# harp_load_cells_interface_v1_1.net
KiCad netlist of a schematic drawn in EAGLE
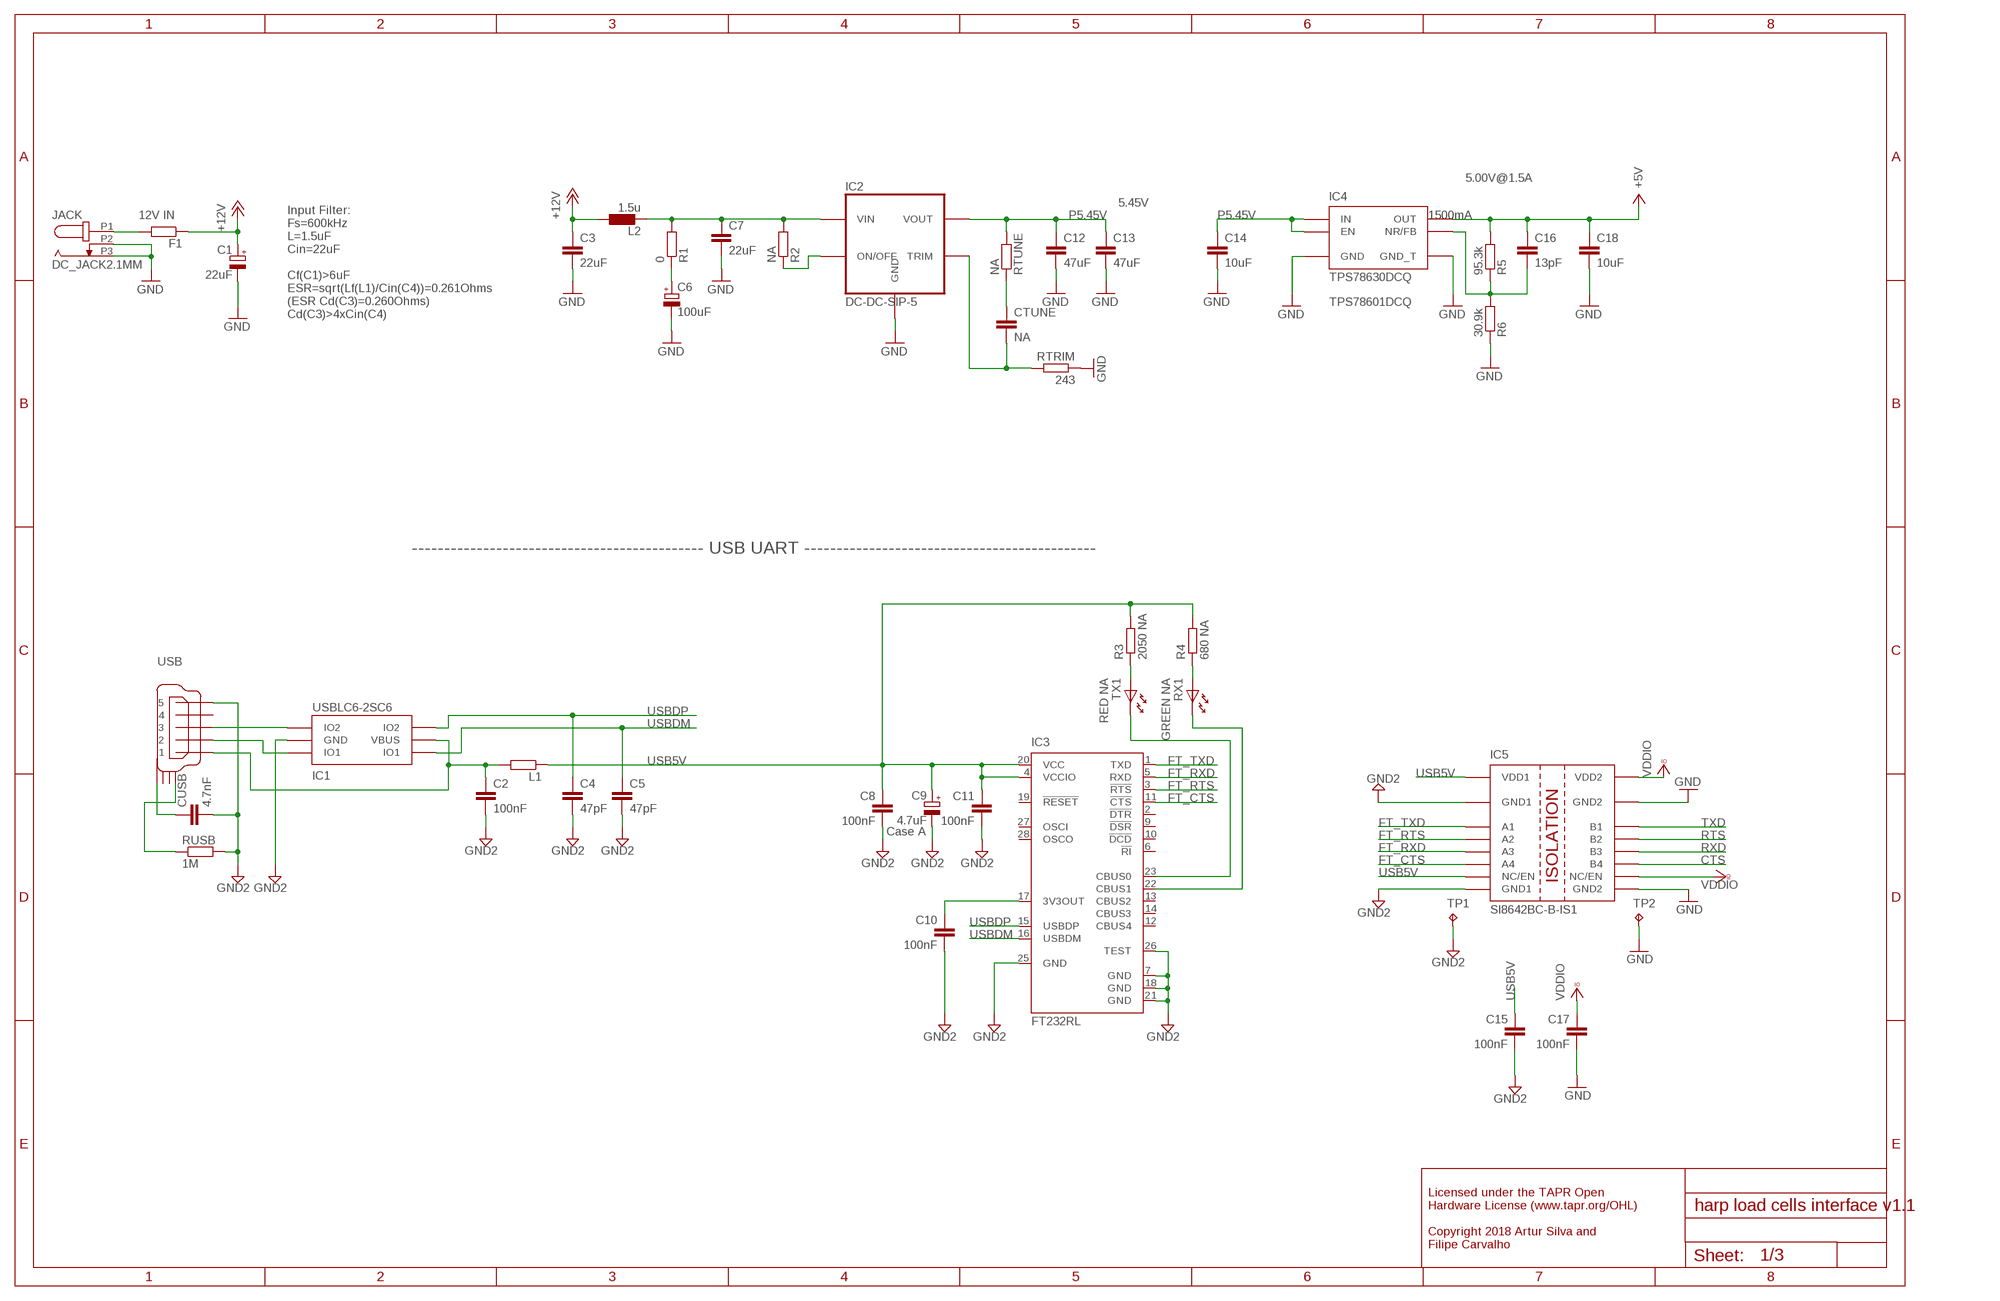
[diagram p0: schematic, sheet 1]
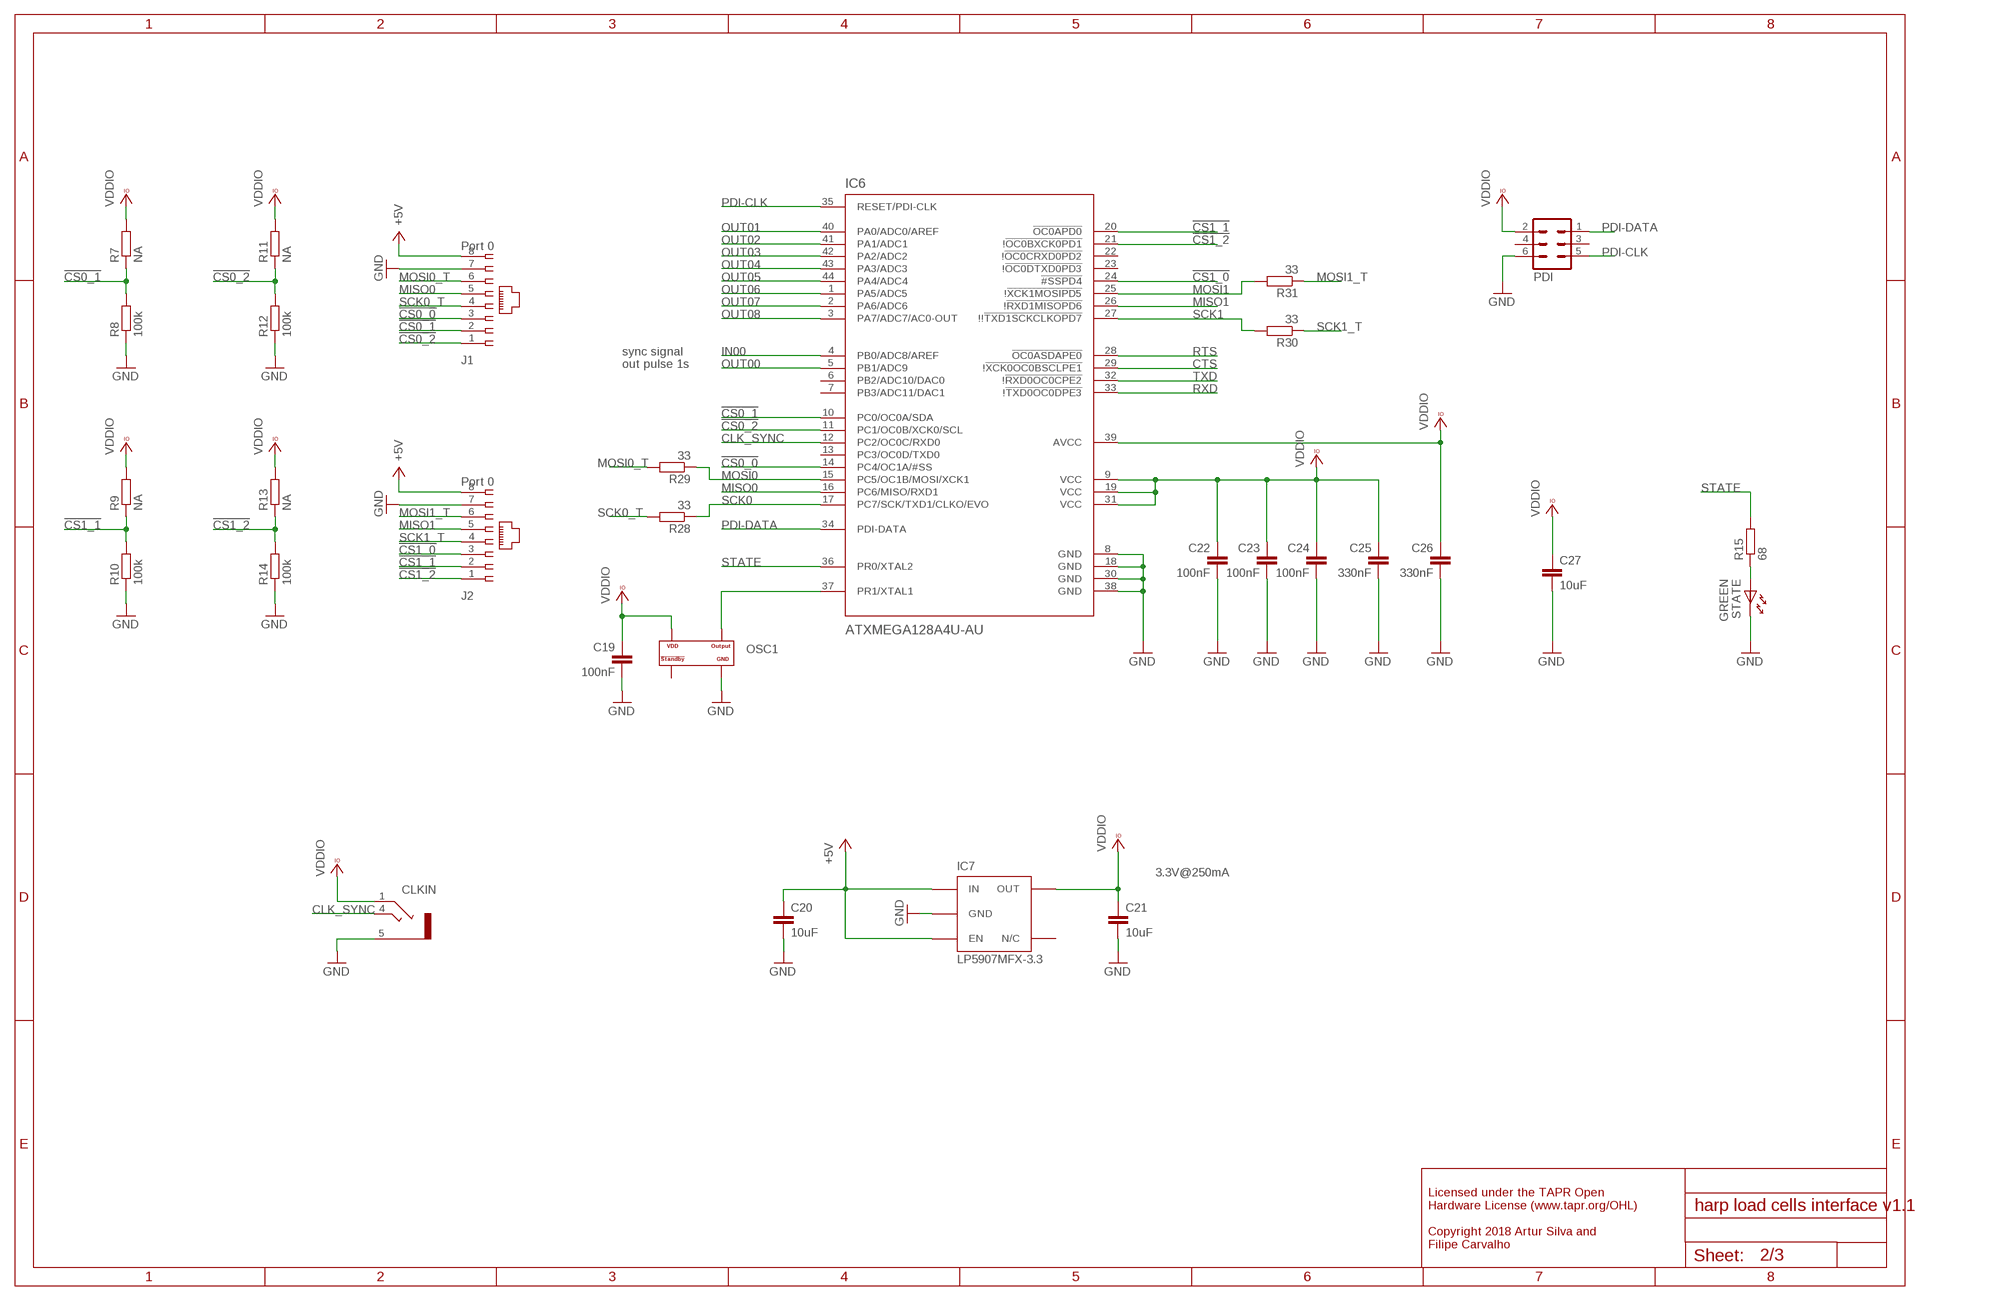
[diagram p1: schematic, sheet 2]
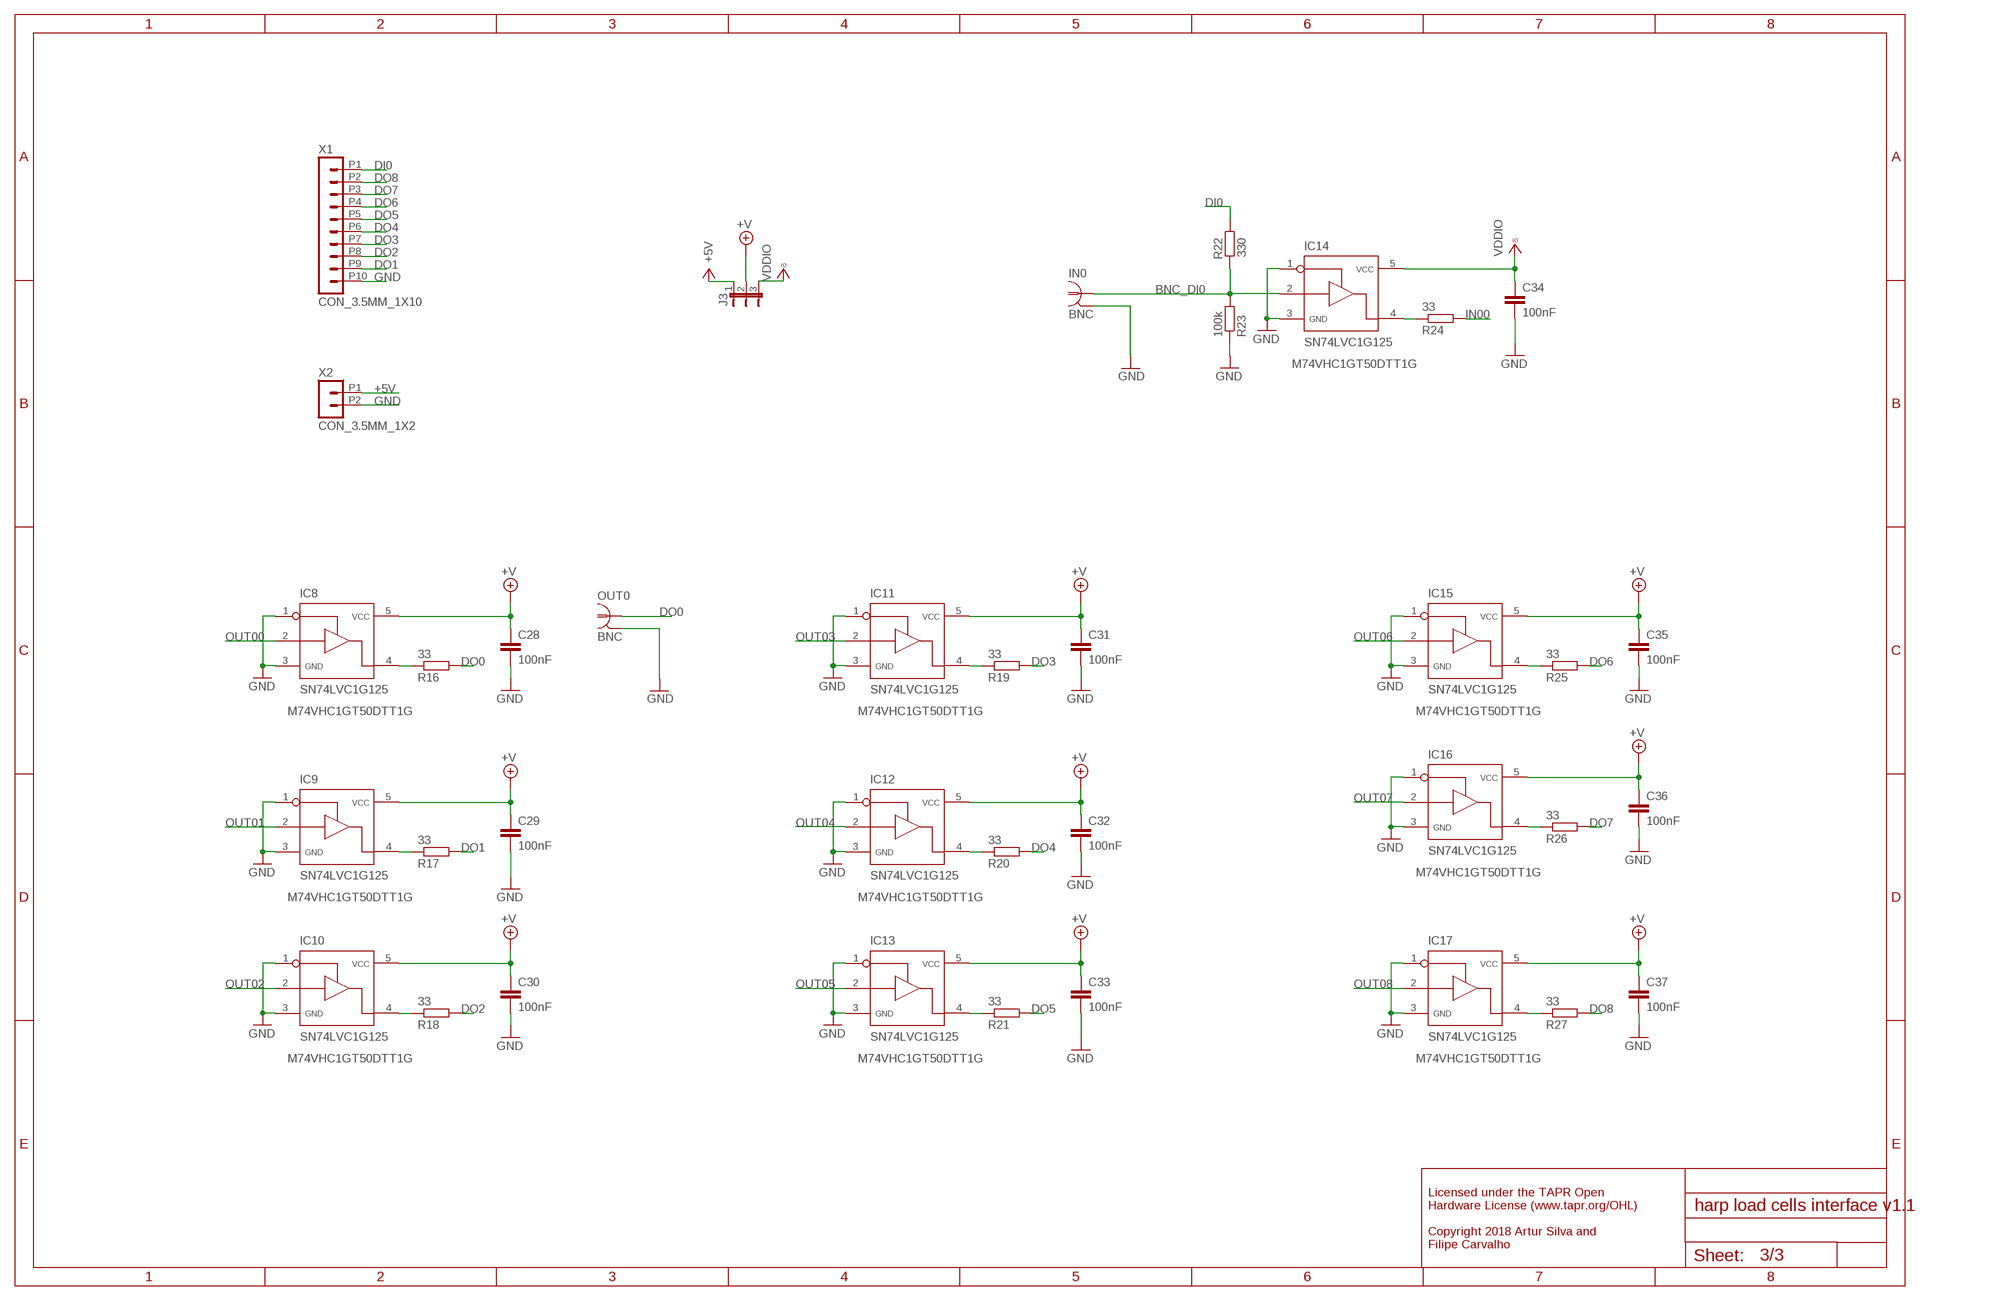
[diagram p2: schematic, sheet 3]

(export (version "E")
  (design (tool "Eeschema 10.0.6"))
  (components
    (comp (ref "C19")
      (value "100nF")
      (footprint "eagle-import:C0402")
      (libsource (lib "eagle-import") (part "C-EUC0402"))
    )
    (comp (ref "C20")
      (value "10uF")
      (footprint "eagle-import:C0603")
      (libsource (lib "eagle-import") (part "C-EUC0603"))
    )
    (comp (ref "C21")
      (value "10uF")
      (footprint "eagle-import:C0603")
      (libsource (lib "eagle-import") (part "C-EUC0603"))
    )
    (comp (ref "C22")
      (value "100nF")
      (footprint "eagle-import:C0402")
      (libsource (lib "eagle-import") (part "C-EUC0402"))
    )
    (comp (ref "C23")
      (value "100nF")
      (footprint "eagle-import:C0402")
      (libsource (lib "eagle-import") (part "C-EUC0402"))
    )
    (comp (ref "C24")
      (value "100nF")
      (footprint "eagle-import:C0402")
      (libsource (lib "eagle-import") (part "C-EUC0402"))
    )
    (comp (ref "C25")
      (value "330nF")
      (footprint "eagle-import:C0402")
      (libsource (lib "eagle-import") (part "C-EUC0402"))
    )
    (comp (ref "C26")
      (value "330nF")
      (footprint "eagle-import:C0402")
      (libsource (lib "eagle-import") (part "C-EUC0402"))
    )
    (comp (ref "C27")
      (value "10uF")
      (footprint "eagle-import:C0603")
      (libsource (lib "eagle-import") (part "C-EUC0603"))
    )
    (comp (ref "CLKIN")
      (value "STEREO_JACK")
      (footprint "eagle-import:35RASMT2BHNTRX")
      (libsource (lib "eagle-import") (part "STEREO_JACK"))
    )
    (comp (ref "IC6")
      (value "ATXMEGA128A4U-AU")
      (footprint "eagle-import:QFP80P1200X1200X120-44N")
      (libsource (lib "eagle-import") (part "AT-XMEGA-XXA4-AU"))
    )
    (comp (ref "IC7")
      (value "LP5907MFX-3.3")
      (footprint "eagle-import:TSOT23-5")
      (libsource (lib "eagle-import") (part "TLV700XX"))
    )
    (comp (ref "J1")
      (value "Port 0")
      (footprint "eagle-import:520426-4")
      (libsource (lib "eagle-import") (part "520426-4"))
    )
    (comp (ref "J2")
      (value "Port 0")
      (footprint "eagle-import:520426-4")
      (libsource (lib "eagle-import") (part "520426-4"))
    )
    (comp (ref "OSC1")
      (value "OSCILLATOR")
      (footprint "eagle-import:OSCILLATOR_3.2X2.5")
      (libsource (lib "eagle-import") (part "OSCILLATOR"))
    )
    (comp (ref "PDI")
      (value "MA03-2")
      (footprint "eagle-import:MA03-2")
      (libsource (lib "eagle-import") (part "MA03-2"))
    )
    (comp (ref "R7")
      (value "NA")
      (footprint "eagle-import:R0402")
      (libsource (lib "eagle-import") (part "R-EU_R0402"))
    )
    (comp (ref "R8")
      (value "100k")
      (footprint "eagle-import:R0402")
      (libsource (lib "eagle-import") (part "R-EU_R0402"))
    )
    (comp (ref "R9")
      (value "NA")
      (footprint "eagle-import:R0402")
      (libsource (lib "eagle-import") (part "R-EU_R0402"))
    )
    (comp (ref "R10")
      (value "100k")
      (footprint "eagle-import:R0402")
      (libsource (lib "eagle-import") (part "R-EU_R0402"))
    )
    (comp (ref "R11")
      (value "NA")
      (footprint "eagle-import:R0402")
      (libsource (lib "eagle-import") (part "R-EU_R0402"))
    )
    (comp (ref "R12")
      (value "100k")
      (footprint "eagle-import:R0402")
      (libsource (lib "eagle-import") (part "R-EU_R0402"))
    )
    (comp (ref "R13")
      (value "NA")
      (footprint "eagle-import:R0402")
      (libsource (lib "eagle-import") (part "R-EU_R0402"))
    )
    (comp (ref "R14")
      (value "100k")
      (footprint "eagle-import:R0402")
      (libsource (lib "eagle-import") (part "R-EU_R0402"))
    )
    (comp (ref "R15")
      (value "68")
      (footprint "eagle-import:R0402")
      (libsource (lib "eagle-import") (part "R-EU_R0402"))
    )
    (comp (ref "R28")
      (value "33")
      (footprint "eagle-import:R0402")
      (libsource (lib "eagle-import") (part "R-EU_R0402"))
    )
    (comp (ref "R29")
      (value "33")
      (footprint "eagle-import:R0402")
      (libsource (lib "eagle-import") (part "R-EU_R0402"))
    )
    (comp (ref "R30")
      (value "33")
      (footprint "eagle-import:R0402")
      (libsource (lib "eagle-import") (part "R-EU_R0402"))
    )
    (comp (ref "R31")
      (value "33")
      (footprint "eagle-import:R0402")
      (libsource (lib "eagle-import") (part "R-EU_R0402"))
    )
    (comp (ref "STATE")
      (value "GREEN")
      (footprint "eagle-import:LED_HAND")
      (libsource (lib "eagle-import") (part "LEDHAND"))
    )
    (comp (ref "C28")
      (value "100nF")
      (footprint "eagle-import:C0402")
      (libsource (lib "eagle-import") (part "C-EUC0402"))
    )
    (comp (ref "C29")
      (value "100nF")
      (footprint "eagle-import:C0402")
      (libsource (lib "eagle-import") (part "C-EUC0402"))
    )
    (comp (ref "C30")
      (value "100nF")
      (footprint "eagle-import:C0402")
      (libsource (lib "eagle-import") (part "C-EUC0402"))
    )
    (comp (ref "C31")
      (value "100nF")
      (footprint "eagle-import:C0402")
      (libsource (lib "eagle-import") (part "C-EUC0402"))
    )
    (comp (ref "C32")
      (value "100nF")
      (footprint "eagle-import:C0402")
      (libsource (lib "eagle-import") (part "C-EUC0402"))
    )
    (comp (ref "C33")
      (value "100nF")
      (footprint "eagle-import:C0402")
      (libsource (lib "eagle-import") (part "C-EUC0402"))
    )
    (comp (ref "C34")
      (value "100nF")
      (footprint "eagle-import:C0402")
      (libsource (lib "eagle-import") (part "C-EUC0402"))
    )
    (comp (ref "C35")
      (value "100nF")
      (footprint "eagle-import:C0402")
      (libsource (lib "eagle-import") (part "C-EUC0402"))
    )
    (comp (ref "C36")
      (value "100nF")
      (footprint "eagle-import:C0402")
      (libsource (lib "eagle-import") (part "C-EUC0402"))
    )
    (comp (ref "C37")
      (value "100nF")
      (footprint "eagle-import:C0402")
      (libsource (lib "eagle-import") (part "C-EUC0402"))
    )
    (comp (ref "IC8")
      (value "SN74LVC1G125")
      (footprint "eagle-import:SOT23-5")
      (libsource (lib "eagle-import") (part "SN74LVC1G125"))
    )
    (comp (ref "IC9")
      (value "SN74LVC1G125")
      (footprint "eagle-import:SOT23-5")
      (libsource (lib "eagle-import") (part "SN74LVC1G125"))
    )
    (comp (ref "IC10")
      (value "SN74LVC1G125")
      (footprint "eagle-import:SOT23-5")
      (libsource (lib "eagle-import") (part "SN74LVC1G125"))
    )
    (comp (ref "IC11")
      (value "SN74LVC1G125")
      (footprint "eagle-import:SOT23-5")
      (libsource (lib "eagle-import") (part "SN74LVC1G125"))
    )
    (comp (ref "IC12")
      (value "SN74LVC1G125")
      (footprint "eagle-import:SOT23-5")
      (libsource (lib "eagle-import") (part "SN74LVC1G125"))
    )
    (comp (ref "IC13")
      (value "SN74LVC1G125")
      (footprint "eagle-import:SOT23-5")
      (libsource (lib "eagle-import") (part "SN74LVC1G125"))
    )
    (comp (ref "IC14")
      (value "SN74LVC1G125")
      (footprint "eagle-import:SOT23-5")
      (libsource (lib "eagle-import") (part "SN74LVC1G125"))
    )
    (comp (ref "IC15")
      (value "SN74LVC1G125")
      (footprint "eagle-import:SOT23-5")
      (libsource (lib "eagle-import") (part "SN74LVC1G125"))
    )
    (comp (ref "IC16")
      (value "SN74LVC1G125")
      (footprint "eagle-import:SOT23-5")
      (libsource (lib "eagle-import") (part "SN74LVC1G125"))
    )
    (comp (ref "IC17")
      (value "SN74LVC1G125")
      (footprint "eagle-import:SOT23-5")
      (libsource (lib "eagle-import") (part "SN74LVC1G125"))
    )
    (comp (ref "IN0")
      (value "BNC")
      (footprint "eagle-import:BNC_RA")
      (libsource (lib "eagle-import") (part "BNC"))
    )
    (comp (ref "J3")
      (value "JP2E")
      (footprint "eagle-import:JP2")
      (libsource (lib "eagle-import") (part "JP2E"))
    )
    (comp (ref "OUT0")
      (value "BNC")
      (footprint "eagle-import:BNC_RA")
      (libsource (lib "eagle-import") (part "BNC"))
    )
    (comp (ref "R16")
      (value "33")
      (footprint "eagle-import:R0402")
      (libsource (lib "eagle-import") (part "R-EU_R0402"))
    )
    (comp (ref "R17")
      (value "33")
      (footprint "eagle-import:R0402")
      (libsource (lib "eagle-import") (part "R-EU_R0402"))
    )
    (comp (ref "R18")
      (value "33")
      (footprint "eagle-import:R0402")
      (libsource (lib "eagle-import") (part "R-EU_R0402"))
    )
    (comp (ref "R19")
      (value "33")
      (footprint "eagle-import:R0402")
      (libsource (lib "eagle-import") (part "R-EU_R0402"))
    )
    (comp (ref "R20")
      (value "33")
      (footprint "eagle-import:R0402")
      (libsource (lib "eagle-import") (part "R-EU_R0402"))
    )
    (comp (ref "R21")
      (value "33")
      (footprint "eagle-import:R0402")
      (libsource (lib "eagle-import") (part "R-EU_R0402"))
    )
    (comp (ref "R22")
      (value "330")
      (footprint "eagle-import:R0402")
      (libsource (lib "eagle-import") (part "R-EU_R0402"))
    )
    (comp (ref "R23")
      (value "100k")
      (footprint "eagle-import:R0402")
      (libsource (lib "eagle-import") (part "R-EU_R0402"))
    )
    (comp (ref "R24")
      (value "33")
      (footprint "eagle-import:R0402")
      (libsource (lib "eagle-import") (part "R-EU_R0402"))
    )
    (comp (ref "R25")
      (value "33")
      (footprint "eagle-import:R0402")
      (libsource (lib "eagle-import") (part "R-EU_R0402"))
    )
    (comp (ref "R26")
      (value "33")
      (footprint "eagle-import:R0402")
      (libsource (lib "eagle-import") (part "R-EU_R0402"))
    )
    (comp (ref "R27")
      (value "33")
      (footprint "eagle-import:R0402")
      (libsource (lib "eagle-import") (part "R-EU_R0402"))
    )
    (comp (ref "X1")
      (value "CON_3.5MM_1X10")
      (footprint "eagle-import:CON_3.5MM_1X10")
      (libsource (lib "eagle-import") (part "CON_3.5MM_1X10"))
    )
    (comp (ref "X2")
      (value "CON_3.5MM_1X2")
      (footprint "eagle-import:CON_3.5MM_1X2")
      (libsource (lib "eagle-import") (part "CON_3.5MM_1X2"))
    )
    (comp (ref "C1")
      (value "22uF")
      (footprint "eagle-import:CAP_100UF_HAND")
      (libsource (lib "eagle-import") (part "CAP_100UFHAND"))
    )
    (comp (ref "C2")
      (value "100nF")
      (footprint "eagle-import:C0402")
      (libsource (lib "eagle-import") (part "C-EUC0402"))
    )
    (comp (ref "C3")
      (value "22uF")
      (footprint "eagle-import:C1210")
      (libsource (lib "eagle-import") (part "C-EUC1210"))
    )
    (comp (ref "C4")
      (value "47pF")
      (footprint "eagle-import:C0402")
      (libsource (lib "eagle-import") (part "C-EUC0402"))
    )
    (comp (ref "C5")
      (value "47pF")
      (footprint "eagle-import:C0402")
      (libsource (lib "eagle-import") (part "C-EUC0402"))
    )
    (comp (ref "C6")
      (value "100uF")
      (footprint "eagle-import:PANASONIC_E")
      (libsource (lib "eagle-import") (part "CPOL-EUE"))
    )
    (comp (ref "C7")
      (value "22uF")
      (footprint "eagle-import:C1210")
      (libsource (lib "eagle-import") (part "C-EUC1210"))
    )
    (comp (ref "C8")
      (value "100nF")
      (footprint "eagle-import:C0402")
      (libsource (lib "eagle-import") (part "C-EUC0402"))
    )
    (comp (ref "C9")
      (value "4.7uF")
      (footprint "eagle-import:A_3216-18W")
      (libsource (lib "eagle-import") (part "CPOL-EUA/3216-18W"))
    )
    (comp (ref "C10")
      (value "100nF")
      (footprint "eagle-import:C0402")
      (libsource (lib "eagle-import") (part "C-EUC0402"))
    )
    (comp (ref "C11")
      (value "100nF")
      (footprint "eagle-import:C0402")
      (libsource (lib "eagle-import") (part "C-EUC0402"))
    )
    (comp (ref "C12")
      (value "47uF")
      (footprint "eagle-import:C1210")
      (libsource (lib "eagle-import") (part "C-EUC1210"))
    )
    (comp (ref "C13")
      (value "47uF")
      (footprint "eagle-import:C1210")
      (libsource (lib "eagle-import") (part "C-EUC1210"))
    )
    (comp (ref "C14")
      (value "10uF")
      (footprint "eagle-import:C0603")
      (libsource (lib "eagle-import") (part "C-EUC0603"))
    )
    (comp (ref "C15")
      (value "100nF")
      (footprint "eagle-import:C0402")
      (libsource (lib "eagle-import") (part "C-EUC0402"))
    )
    (comp (ref "C16")
      (value "13pF")
      (footprint "eagle-import:C0402")
      (libsource (lib "eagle-import") (part "C-EUC0402"))
    )
    (comp (ref "C17")
      (value "100nF")
      (footprint "eagle-import:C0402")
      (libsource (lib "eagle-import") (part "C-EUC0402"))
    )
    (comp (ref "C18")
      (value "10uF")
      (footprint "eagle-import:C0603")
      (libsource (lib "eagle-import") (part "C-EUC0603"))
    )
    (comp (ref "CTUNE")
      (value "NA")
      (footprint "eagle-import:C0402")
      (libsource (lib "eagle-import") (part "C-EUC0402"))
    )
    (comp (ref "CUSB")
      (value "4.7nF")
      (footprint "eagle-import:C0402")
      (libsource (lib "eagle-import") (part "C-EUC0402"))
    )
    (comp (ref "F1")
      (value "1A FB")
      (footprint "eagle-import:R0603")
      (libsource (lib "eagle-import") (part "R-EU_R0603"))
    )
    (comp (ref "IC1")
      (value "USBLC6-2SC6")
      (footprint "eagle-import:SOT23-6L")
      (libsource (lib "eagle-import") (part "USBLC6-2"))
    )
    (comp (ref "IC2")
      (value "DC-DC-SIP-5")
      (footprint "eagle-import:SIP-5")
      (libsource (lib "eagle-import") (part "DC-DC-SIP-5"))
    )
    (comp (ref "IC3")
      (value "FT232RL")
      (footprint "eagle-import:SSOP28")
      (libsource (lib "eagle-import") (part "FT232RL"))
    )
    (comp (ref "IC4")
      (value "TPS78630DCQ")
      (footprint "eagle-import:SOT223-6")
      (libsource (lib "eagle-import") (part "TPS795XX"))
    )
    (comp (ref "IC5")
      (value "SI8642BC-B-IS1")
      (footprint "eagle-import:NSOIC-16")
      (libsource (lib "eagle-import") (part "SI8645"))
    )
    (comp (ref "JACK")
      (value "DC_JACK2.1MM")
      (footprint "eagle-import:DC_POWER_INPUT_2.1MM")
      (libsource (lib "eagle-import") (part "DC_JACK2.1MM"))
    )
    (comp (ref "L1")
      (value "???")
      (footprint "eagle-import:R0805")
      (libsource (lib "eagle-import") (part "R-EU_R0805"))
    )
    (comp (ref "L2")
      (value "1.5u")
      (footprint "eagle-import:IND_LPS4012")
      (libsource (lib "eagle-import") (part "INDLPS4012"))
    )
    (comp (ref "R1")
      (value "0")
      (footprint "eagle-import:R0402")
      (libsource (lib "eagle-import") (part "R-EU_R0402"))
    )
    (comp (ref "R2")
      (value "NA")
      (footprint "eagle-import:R0402")
      (libsource (lib "eagle-import") (part "R-EU_R0402"))
    )
    (comp (ref "R3")
      (value "2050 NA")
      (footprint "eagle-import:R0402")
      (libsource (lib "eagle-import") (part "R-EU_R0402"))
    )
    (comp (ref "R4")
      (value "680 NA")
      (footprint "eagle-import:R0402")
      (libsource (lib "eagle-import") (part "R-EU_R0402"))
    )
    (comp (ref "R5")
      (value "95.3k")
      (footprint "eagle-import:R0402")
      (libsource (lib "eagle-import") (part "R-EU_R0402"))
    )
    (comp (ref "R6")
      (value "30.9k")
      (footprint "eagle-import:R0402")
      (libsource (lib "eagle-import") (part "R-EU_R0402"))
    )
    (comp (ref "RTRIM")
      (value "243")
      (footprint "eagle-import:R0402")
      (libsource (lib "eagle-import") (part "R-EU_R0402"))
    )
    (comp (ref "RTUNE")
      (value "NA")
      (footprint "eagle-import:R0402")
      (libsource (lib "eagle-import") (part "R-EU_R0402"))
    )
    (comp (ref "RUSB")
      (value "1M")
      (footprint "eagle-import:R0402")
      (libsource (lib "eagle-import") (part "R-EU_R0402"))
    )
    (comp (ref "RX1")
      (value "GREEN NA")
      (footprint "eagle-import:LED_HAND")
      (libsource (lib "eagle-import") (part "LEDHAND"))
    )
    (comp (ref "TP1")
      (value "TPTP08SQ")
      (footprint "eagle-import:TP08SQ")
      (libsource (lib "eagle-import") (part "TPTP08SQ"))
    )
    (comp (ref "TP2")
      (value "TPTP08SQ")
      (footprint "eagle-import:TP08SQ")
      (libsource (lib "eagle-import") (part "TPTP08SQ"))
    )
    (comp (ref "TX1")
      (value "RED NA")
      (footprint "eagle-import:LED_HAND")
      (libsource (lib "eagle-import") (part "LEDHAND"))
    )
    (comp (ref "USB")
      (value "USB_MINI_B")
      (footprint "eagle-import:240-0002-1")
      (libsource (lib "eagle-import") (part "USB_MINI_B"))
    )
  )
  (nets
    (net (code "1") (name "+5V") (class "Default")
      (node (ref "C16") (pin "1") (pinfunction "1_1") (pintype "passive"))
      (node (ref "C18") (pin "1") (pinfunction "1_1") (pintype "passive"))
      (node (ref "C20") (pin "1") (pinfunction "1_1") (pintype "passive"))
      (node (ref "IC4") (pin "P$4") (pinfunction "OUT_P$4") (pintype "bidirectional"))
      (node (ref "IC7") (pin "1") (pinfunction "IN_1") (pintype "bidirectional"))
      (node (ref "IC7") (pin "3") (pinfunction "EN_3") (pintype "bidirectional"))
      (node (ref "J1") (pin "8") (pinfunction "8_8") (pintype "passive"))
      (node (ref "J2") (pin "8") (pinfunction "8_8") (pintype "passive"))
      (node (ref "J3") (pin "1") (pinfunction "1_1") (pintype "passive"))
      (node (ref "R5") (pin "2") (pinfunction "2_2") (pintype "passive"))
      (node (ref "X2") (pin "P1") (pinfunction "1_P1") (pintype "passive"))
    )
    (net (code "2") (name "+12V") (class "Default")
      (node (ref "C1") (pin "+") (pinfunction "+_+") (pintype "passive"))
      (node (ref "C3") (pin "1") (pinfunction "1_1") (pintype "passive"))
      (node (ref "F1") (pin "1") (pinfunction "1_1") (pintype "passive"))
      (node (ref "L2") (pin "1") (pinfunction "1_1") (pintype "passive"))
    )
    (net (code "3") (name "+V") (class "Default")
      (node (ref "C28") (pin "1") (pinfunction "1_1") (pintype "passive"))
      (node (ref "C29") (pin "1") (pinfunction "1_1") (pintype "passive"))
      (node (ref "C30") (pin "1") (pinfunction "1_1") (pintype "passive"))
      (node (ref "C31") (pin "1") (pinfunction "1_1") (pintype "passive"))
      (node (ref "C32") (pin "1") (pinfunction "1_1") (pintype "passive"))
      (node (ref "C33") (pin "1") (pinfunction "1_1") (pintype "passive"))
      (node (ref "C35") (pin "1") (pinfunction "1_1") (pintype "passive"))
      (node (ref "C36") (pin "1") (pinfunction "1_1") (pintype "passive"))
      (node (ref "C37") (pin "1") (pinfunction "1_1") (pintype "passive"))
      (node (ref "IC10") (pin "5") (pinfunction "P$5_5") (pintype "bidirectional"))
      (node (ref "IC11") (pin "5") (pinfunction "P$5_5") (pintype "bidirectional"))
      (node (ref "IC12") (pin "5") (pinfunction "P$5_5") (pintype "bidirectional"))
      (node (ref "IC13") (pin "5") (pinfunction "P$5_5") (pintype "bidirectional"))
      (node (ref "IC15") (pin "5") (pinfunction "P$5_5") (pintype "bidirectional"))
      (node (ref "IC16") (pin "5") (pinfunction "P$5_5") (pintype "bidirectional"))
      (node (ref "IC17") (pin "5") (pinfunction "P$5_5") (pintype "bidirectional"))
      (node (ref "IC8") (pin "5") (pinfunction "P$5_5") (pintype "bidirectional"))
      (node (ref "IC9") (pin "5") (pinfunction "P$5_5") (pintype "bidirectional"))
      (node (ref "J3") (pin "2") (pinfunction "2_2") (pintype "passive"))
    )
    (net (code "4") (name "BNC_DI0") (class "Default")
      (node (ref "IC14") (pin "2") (pinfunction "P$2_2") (pintype "bidirectional"))
      (node (ref "IN0") (pin "1") (pinfunction "1_1") (pintype "passive"))
      (node (ref "R22") (pin "2") (pinfunction "2_2") (pintype "passive"))
      (node (ref "R23") (pin "2") (pinfunction "2_2") (pintype "passive"))
    )
    (net (code "5") (name "CLK_SYNC") (class "Default")
      (node (ref "CLKIN") (pin "4") (pinfunction "4_4") (pintype "passive"))
      (node (ref "IC6") (pin "12") (pinfunction "PC2/OC0C/RXD0_12") (pintype "bidirectional"))
    )
    (net (code "6") (name "CTS") (class "Default")
      (node (ref "IC5") (pin "11") (pinfunction "B4_11") (pintype "bidirectional"))
      (node (ref "IC6") (pin "29") (pinfunction "~XCK0OC0BSCLPE1_29") (pintype "bidirectional"))
    )
    (net (code "7") (name "DI0") (class "Default")
      (node (ref "R22") (pin "1") (pinfunction "1_1") (pintype "passive"))
      (node (ref "X1") (pin "P1") (pinfunction "1_P1") (pintype "passive"))
    )
    (net (code "8") (name "DO0") (class "Default")
      (node (ref "OUT0") (pin "1") (pinfunction "1_1") (pintype "passive"))
      (node (ref "R16") (pin "2") (pinfunction "2_2") (pintype "passive"))
    )
    (net (code "9") (name "DO1") (class "Default")
      (node (ref "R17") (pin "2") (pinfunction "2_2") (pintype "passive"))
      (node (ref "X1") (pin "P9") (pinfunction "9_P9") (pintype "passive"))
    )
    (net (code "10") (name "DO2") (class "Default")
      (node (ref "R18") (pin "2") (pinfunction "2_2") (pintype "passive"))
      (node (ref "X1") (pin "P8") (pinfunction "8_P8") (pintype "passive"))
    )
    (net (code "11") (name "DO3") (class "Default")
      (node (ref "R19") (pin "2") (pinfunction "2_2") (pintype "passive"))
      (node (ref "X1") (pin "P7") (pinfunction "7_P7") (pintype "passive"))
    )
    (net (code "12") (name "DO4") (class "Default")
      (node (ref "R20") (pin "2") (pinfunction "2_2") (pintype "passive"))
      (node (ref "X1") (pin "P6") (pinfunction "6_P6") (pintype "passive"))
    )
    (net (code "13") (name "DO5") (class "Default")
      (node (ref "R21") (pin "2") (pinfunction "2_2") (pintype "passive"))
      (node (ref "X1") (pin "P5") (pinfunction "5_P5") (pintype "passive"))
    )
    (net (code "14") (name "DO6") (class "Default")
      (node (ref "R25") (pin "2") (pinfunction "2_2") (pintype "passive"))
      (node (ref "X1") (pin "P4") (pinfunction "4_P4") (pintype "passive"))
    )
    (net (code "15") (name "DO7") (class "Default")
      (node (ref "R26") (pin "2") (pinfunction "2_2") (pintype "passive"))
      (node (ref "X1") (pin "P3") (pinfunction "3_P3") (pintype "passive"))
    )
    (net (code "16") (name "DO8") (class "Default")
      (node (ref "R27") (pin "2") (pinfunction "2_2") (pintype "passive"))
      (node (ref "X1") (pin "P2") (pinfunction "2_P2") (pintype "passive"))
    )
    (net (code "17") (name "FT_CTS") (class "Default")
      (node (ref "IC3") (pin "11") (pinfunction "~{CTS}_11") (pintype "input"))
      (node (ref "IC5") (pin "6") (pinfunction "A4_6") (pintype "bidirectional"))
    )
    (net (code "18") (name "FT_RTS") (class "Default")
      (node (ref "IC3") (pin "3") (pinfunction "~{RTS}_3") (pintype "output"))
      (node (ref "IC5") (pin "4") (pinfunction "A2_4") (pintype "bidirectional"))
    )
    (net (code "19") (name "FT_RXD") (class "Default")
      (node (ref "IC3") (pin "5") (pinfunction "RXD_5") (pintype "input"))
      (node (ref "IC5") (pin "5") (pinfunction "A3_5") (pintype "bidirectional"))
    )
    (net (code "20") (name "FT_TXD") (class "Default")
      (node (ref "IC3") (pin "1") (pinfunction "TXD_1") (pintype "output"))
      (node (ref "IC5") (pin "3") (pinfunction "A1_3") (pintype "bidirectional"))
    )
    (net (code "21") (name "GND") (class "Default")
      (node (ref "C1") (pin "-") (pinfunction "-_-") (pintype "passive"))
      (node (ref "C12") (pin "2") (pinfunction "2_2") (pintype "passive"))
      (node (ref "C13") (pin "2") (pinfunction "2_2") (pintype "passive"))
      (node (ref "C14") (pin "2") (pinfunction "2_2") (pintype "passive"))
      (node (ref "C17") (pin "2") (pinfunction "2_2") (pintype "passive"))
      (node (ref "C18") (pin "2") (pinfunction "2_2") (pintype "passive"))
      (node (ref "C19") (pin "2") (pinfunction "2_2") (pintype "passive"))
      (node (ref "C20") (pin "2") (pinfunction "2_2") (pintype "passive"))
      (node (ref "C21") (pin "2") (pinfunction "2_2") (pintype "passive"))
      (node (ref "C22") (pin "2") (pinfunction "2_2") (pintype "passive"))
      (node (ref "C23") (pin "2") (pinfunction "2_2") (pintype "passive"))
      (node (ref "C24") (pin "2") (pinfunction "2_2") (pintype "passive"))
      (node (ref "C25") (pin "2") (pinfunction "2_2") (pintype "passive"))
      (node (ref "C26") (pin "2") (pinfunction "2_2") (pintype "passive"))
      (node (ref "C27") (pin "2") (pinfunction "2_2") (pintype "passive"))
      (node (ref "C28") (pin "2") (pinfunction "2_2") (pintype "passive"))
      (node (ref "C29") (pin "2") (pinfunction "2_2") (pintype "passive"))
      (node (ref "C3") (pin "2") (pinfunction "2_2") (pintype "passive"))
      (node (ref "C30") (pin "2") (pinfunction "2_2") (pintype "passive"))
      (node (ref "C31") (pin "2") (pinfunction "2_2") (pintype "passive"))
      (node (ref "C32") (pin "2") (pinfunction "2_2") (pintype "passive"))
      (node (ref "C33") (pin "2") (pinfunction "2_2") (pintype "passive"))
      (node (ref "C34") (pin "2") (pinfunction "2_2") (pintype "passive"))
      (node (ref "C35") (pin "2") (pinfunction "2_2") (pintype "passive"))
      (node (ref "C36") (pin "2") (pinfunction "2_2") (pintype "passive"))
      (node (ref "C37") (pin "2") (pinfunction "2_2") (pintype "passive"))
      (node (ref "C6") (pin "-") (pinfunction "-_-") (pintype "passive"))
      (node (ref "C7") (pin "2") (pinfunction "2_2") (pintype "passive"))
      (node (ref "CLKIN") (pin "5") (pinfunction "5_5") (pintype "passive"))
      (node (ref "IC10") (pin "1") (pinfunction "P$1_1") (pintype "bidirectional"))
      (node (ref "IC10") (pin "3") (pinfunction "P$3_3") (pintype "bidirectional"))
      (node (ref "IC11") (pin "1") (pinfunction "P$1_1") (pintype "bidirectional"))
      (node (ref "IC11") (pin "3") (pinfunction "P$3_3") (pintype "bidirectional"))
      (node (ref "IC12") (pin "1") (pinfunction "P$1_1") (pintype "bidirectional"))
      (node (ref "IC12") (pin "3") (pinfunction "P$3_3") (pintype "bidirectional"))
      (node (ref "IC13") (pin "1") (pinfunction "P$1_1") (pintype "bidirectional"))
      (node (ref "IC13") (pin "3") (pinfunction "P$3_3") (pintype "bidirectional"))
      (node (ref "IC14") (pin "1") (pinfunction "P$1_1") (pintype "bidirectional"))
      (node (ref "IC14") (pin "3") (pinfunction "P$3_3") (pintype "bidirectional"))
      (node (ref "IC15") (pin "1") (pinfunction "P$1_1") (pintype "bidirectional"))
      (node (ref "IC15") (pin "3") (pinfunction "P$3_3") (pintype "bidirectional"))
      (node (ref "IC16") (pin "1") (pinfunction "P$1_1") (pintype "bidirectional"))
      (node (ref "IC16") (pin "3") (pinfunction "P$3_3") (pintype "bidirectional"))
      (node (ref "IC17") (pin "1") (pinfunction "P$1_1") (pintype "bidirectional"))
      (node (ref "IC17") (pin "3") (pinfunction "P$3_3") (pintype "bidirectional"))
      (node (ref "IC2") (pin "P3") (pinfunction "GND_P3") (pintype "passive"))
      (node (ref "IC4") (pin "P$3") (pinfunction "GND_P$3") (pintype "bidirectional"))
      (node (ref "IC4") (pin "P$6") (pinfunction "GND_T_P$6") (pintype "bidirectional"))
      (node (ref "IC5") (pin "15") (pinfunction "GND2_15") (pintype "bidirectional"))
      (node (ref "IC5") (pin "9") (pinfunction "GND2_9") (pintype "bidirectional"))
      (node (ref "IC6") (pin "18") (pinfunction "GND_18") (pintype "power_in"))
      (node (ref "IC6") (pin "30") (pinfunction "GND_30") (pintype "power_in"))
      (node (ref "IC6") (pin "38") (pinfunction "GND_38") (pintype "power_in"))
      (node (ref "IC6") (pin "8") (pinfunction "GND_8") (pintype "power_in"))
      (node (ref "IC7") (pin "2") (pinfunction "GND_2") (pintype "bidirectional"))
      (node (ref "IC8") (pin "1") (pinfunction "P$1_1") (pintype "bidirectional"))
      (node (ref "IC8") (pin "3") (pinfunction "P$3_3") (pintype "bidirectional"))
      (node (ref "IC9") (pin "1") (pinfunction "P$1_1") (pintype "bidirectional"))
      (node (ref "IC9") (pin "3") (pinfunction "P$3_3") (pintype "bidirectional"))
      (node (ref "IN0") (pin "2") (pinfunction "2_2") (pintype "passive"))
      (node (ref "J1") (pin "7") (pinfunction "7_7") (pintype "passive"))
      (node (ref "J2") (pin "7") (pinfunction "7_7") (pintype "passive"))
      (node (ref "JACK") (pin "P2") (pinfunction "2_P2") (pintype "passive"))
      (node (ref "JACK") (pin "P3") (pinfunction "3_P3") (pintype "passive"))
      (node (ref "OSC1") (pin "P$2") (pinfunction "GND_P$2") (pintype "passive"))
      (node (ref "OUT0") (pin "2") (pinfunction "2_2") (pintype "passive"))
      (node (ref "PDI") (pin "6") (pinfunction "6_6") (pintype "passive"))
      (node (ref "R10") (pin "1") (pinfunction "1_1") (pintype "passive"))
      (node (ref "R12") (pin "1") (pinfunction "1_1") (pintype "passive"))
      (node (ref "R14") (pin "1") (pinfunction "1_1") (pintype "passive"))
      (node (ref "R23") (pin "1") (pinfunction "1_1") (pintype "passive"))
      (node (ref "R6") (pin "1") (pinfunction "1_1") (pintype "passive"))
      (node (ref "R8") (pin "1") (pinfunction "1_1") (pintype "passive"))
      (node (ref "RTRIM") (pin "1") (pinfunction "1_1") (pintype "passive"))
      (node (ref "STATE") (pin "K") (pinfunction "K_K") (pintype "bidirectional"))
      (node (ref "TP2") (pin "TP") (pinfunction "TP_TP") (pintype "input"))
      (node (ref "X1") (pin "P10") (pinfunction "10_P10") (pintype "passive"))
      (node (ref "X2") (pin "P2") (pinfunction "2_P2") (pintype "passive"))
    )
    (net (code "22") (name "GND2") (class "Default")
      (node (ref "C10") (pin "2") (pinfunction "2_2") (pintype "passive"))
      (node (ref "C11") (pin "2") (pinfunction "2_2") (pintype "passive"))
      (node (ref "C15") (pin "2") (pinfunction "2_2") (pintype "passive"))
      (node (ref "C2") (pin "2") (pinfunction "2_2") (pintype "passive"))
      (node (ref "C4") (pin "2") (pinfunction "2_2") (pintype "passive"))
      (node (ref "C5") (pin "2") (pinfunction "2_2") (pintype "passive"))
      (node (ref "C8") (pin "2") (pinfunction "2_2") (pintype "passive"))
      (node (ref "C9") (pin "-") (pinfunction "-_-") (pintype "passive"))
      (node (ref "CUSB") (pin "2") (pinfunction "2_2") (pintype "passive"))
      (node (ref "IC1") (pin "P$2") (pinfunction "GND_P$2") (pintype "bidirectional"))
      (node (ref "IC3") (pin "18") (pinfunction "GND_18") (pintype "power_in"))
      (node (ref "IC3") (pin "21") (pinfunction "GND_21") (pintype "power_in"))
      (node (ref "IC3") (pin "25") (pinfunction "GND_25") (pintype "power_in"))
      (node (ref "IC3") (pin "26") (pinfunction "TEST_26") (pintype "input"))
      (node (ref "IC3") (pin "7") (pinfunction "GND_7") (pintype "power_in"))
      (node (ref "IC5") (pin "2") (pinfunction "GND1_2") (pintype "bidirectional"))
      (node (ref "IC5") (pin "8") (pinfunction "GND1_8") (pintype "bidirectional"))
      (node (ref "RUSB") (pin "2") (pinfunction "2_2") (pintype "passive"))
      (node (ref "TP1") (pin "TP") (pinfunction "TP_TP") (pintype "input"))
      (node (ref "USB") (pin "P$5") (pinfunction "5_P$5") (pintype "bidirectional"))
    )
    (net (code "23") (name "IN00") (class "Default")
      (node (ref "IC6") (pin "4") (pinfunction "PB0/ADC8/AREF_4") (pintype "bidirectional"))
      (node (ref "R24") (pin "2") (pinfunction "2_2") (pintype "passive"))
    )
    (net (code "24") (name "MISO0") (class "Default")
      (node (ref "IC6") (pin "16") (pinfunction "PC6/MISO/RXD1_16") (pintype "bidirectional"))
      (node (ref "J1") (pin "5") (pinfunction "5_5") (pintype "passive"))
    )
    (net (code "25") (name "MISO1") (class "Default")
      (node (ref "IC6") (pin "26") (pinfunction "~RXD1MISOPD6_26") (pintype "bidirectional"))
      (node (ref "J2") (pin "5") (pinfunction "5_5") (pintype "passive"))
    )
    (net (code "26") (name "MOSI0") (class "Default")
      (node (ref "IC6") (pin "15") (pinfunction "PC5/OC1B/MOSI/XCK1_15") (pintype "bidirectional"))
      (node (ref "R29") (pin "1") (pinfunction "1_1") (pintype "passive"))
    )
    (net (code "27") (name "MOSI0_T") (class "Default")
      (node (ref "J1") (pin "6") (pinfunction "6_6") (pintype "passive"))
      (node (ref "R29") (pin "2") (pinfunction "2_2") (pintype "passive"))
    )
    (net (code "28") (name "MOSI1") (class "Default")
      (node (ref "IC6") (pin "25") (pinfunction "~XCK1MOSIPD5_25") (pintype "bidirectional"))
      (node (ref "R31") (pin "2") (pinfunction "2_2") (pintype "passive"))
    )
    (net (code "29") (name "MOSI1_T") (class "Default")
      (node (ref "J2") (pin "6") (pinfunction "6_6") (pintype "passive"))
      (node (ref "R31") (pin "1") (pinfunction "1_1") (pintype "passive"))
    )
    (net (code "30") (name "Net-(C6-Pad+)") (class "Default")
      (node (ref "C6") (pin "+") (pinfunction "+_+") (pintype "passive"))
      (node (ref "R1") (pin "1") (pinfunction "1_1") (pintype "passive"))
    )
    (net (code "31") (name "Net-(CTUNE-Pad1)") (class "Default")
      (node (ref "CTUNE") (pin "1") (pinfunction "1_1") (pintype "passive"))
      (node (ref "RTUNE") (pin "1") (pinfunction "1_1") (pintype "passive"))
    )
    (net (code "32") (name "Net-(IC1-VBUS)") (class "Default")
      (node (ref "C2") (pin "1") (pinfunction "1_1") (pintype "passive"))
      (node (ref "IC1") (pin "P$5") (pinfunction "VBUS_P$5") (pintype "bidirectional"))
      (node (ref "L1") (pin "2") (pinfunction "2_2") (pintype "passive"))
      (node (ref "USB") (pin "P$1") (pinfunction "1_P$1") (pintype "bidirectional"))
    )
    (net (code "33") (name "Net-(IC2-ON{slash}OFF)") (class "Default")
      (node (ref "IC2") (pin "P1") (pinfunction "ON/OFF_P1") (pintype "passive"))
      (node (ref "R2") (pin "1") (pinfunction "1_1") (pintype "passive"))
    )
    (net (code "34") (name "Net-(IC2-TRIM)") (class "Default")
      (node (ref "CTUNE") (pin "2") (pinfunction "2_2") (pintype "passive"))
      (node (ref "IC2") (pin "P5") (pinfunction "TRIM_P5") (pintype "passive"))
      (node (ref "RTRIM") (pin "2") (pinfunction "2_2") (pintype "passive"))
    )
    (net (code "35") (name "Net-(IC2-VIN)") (class "Default")
      (node (ref "C7") (pin "1") (pinfunction "1_1") (pintype "passive"))
      (node (ref "IC2") (pin "P2") (pinfunction "VIN_P2") (pintype "passive"))
      (node (ref "L2") (pin "2") (pinfunction "2_2") (pintype "passive"))
      (node (ref "R1") (pin "2") (pinfunction "2_2") (pintype "passive"))
      (node (ref "R2") (pin "2") (pinfunction "2_2") (pintype "passive"))
    )
    (net (code "36") (name "Net-(IC3-3V3OUT)") (class "Default")
      (node (ref "C10") (pin "1") (pinfunction "1_1") (pintype "passive"))
      (node (ref "IC3") (pin "17") (pinfunction "3V3OUT_17") (pintype "output"))
    )
    (net (code "37") (name "Net-(IC3-CBUS0)") (class "Default")
      (node (ref "IC3") (pin "23") (pinfunction "CBUS0_23") (pintype "bidirectional"))
      (node (ref "TX1") (pin "K") (pinfunction "K_K") (pintype "bidirectional"))
    )
    (net (code "38") (name "Net-(IC3-CBUS1)") (class "Default")
      (node (ref "IC3") (pin "22") (pinfunction "CBUS1_22") (pintype "bidirectional"))
      (node (ref "RX1") (pin "K") (pinfunction "K_K") (pintype "bidirectional"))
    )
    (net (code "39") (name "Net-(IC4-NR{slash}FB)") (class "Default")
      (node (ref "C16") (pin "2") (pinfunction "2_2") (pintype "passive"))
      (node (ref "IC4") (pin "P$5") (pinfunction "NR/FB_P$5") (pintype "bidirectional"))
      (node (ref "R5") (pin "1") (pinfunction "1_1") (pintype "passive"))
      (node (ref "R6") (pin "2") (pinfunction "2_2") (pintype "passive"))
    )
    (net (code "40") (name "Net-(IC6-PR1{slash}XTAL1)") (class "Default")
      (node (ref "IC6") (pin "37") (pinfunction "PR1/XTAL1_37") (pintype "bidirectional"))
      (node (ref "OSC1") (pin "P$3") (pinfunction "OUTPUT_P$3") (pintype "passive"))
    )
    (net (code "41") (name "Net-(IC8-P$4)") (class "Default")
      (node (ref "IC8") (pin "4") (pinfunction "P$4_4") (pintype "bidirectional"))
      (node (ref "R16") (pin "1") (pinfunction "1_1") (pintype "passive"))
    )
    (net (code "42") (name "Net-(IC9-P$4)") (class "Default")
      (node (ref "IC9") (pin "4") (pinfunction "P$4_4") (pintype "bidirectional"))
      (node (ref "R17") (pin "1") (pinfunction "1_1") (pintype "passive"))
    )
    (net (code "43") (name "Net-(IC10-P$4)") (class "Default")
      (node (ref "IC10") (pin "4") (pinfunction "P$4_4") (pintype "bidirectional"))
      (node (ref "R18") (pin "1") (pinfunction "1_1") (pintype "passive"))
    )
    (net (code "44") (name "Net-(IC11-P$4)") (class "Default")
      (node (ref "IC11") (pin "4") (pinfunction "P$4_4") (pintype "bidirectional"))
      (node (ref "R19") (pin "1") (pinfunction "1_1") (pintype "passive"))
    )
    (net (code "45") (name "Net-(IC12-P$4)") (class "Default")
      (node (ref "IC12") (pin "4") (pinfunction "P$4_4") (pintype "bidirectional"))
      (node (ref "R20") (pin "1") (pinfunction "1_1") (pintype "passive"))
    )
    (net (code "46") (name "Net-(IC13-P$4)") (class "Default")
      (node (ref "IC13") (pin "4") (pinfunction "P$4_4") (pintype "bidirectional"))
      (node (ref "R21") (pin "1") (pinfunction "1_1") (pintype "passive"))
    )
    (net (code "47") (name "Net-(IC14-P$4)") (class "Default")
      (node (ref "IC14") (pin "4") (pinfunction "P$4_4") (pintype "bidirectional"))
      (node (ref "R24") (pin "1") (pinfunction "1_1") (pintype "passive"))
    )
    (net (code "48") (name "Net-(IC15-P$4)") (class "Default")
      (node (ref "IC15") (pin "4") (pinfunction "P$4_4") (pintype "bidirectional"))
      (node (ref "R25") (pin "1") (pinfunction "1_1") (pintype "passive"))
    )
    (net (code "49") (name "Net-(IC16-P$4)") (class "Default")
      (node (ref "IC16") (pin "4") (pinfunction "P$4_4") (pintype "bidirectional"))
      (node (ref "R26") (pin "1") (pinfunction "1_1") (pintype "passive"))
    )
    (net (code "50") (name "Net-(IC17-P$4)") (class "Default")
      (node (ref "IC17") (pin "4") (pinfunction "P$4_4") (pintype "bidirectional"))
      (node (ref "R27") (pin "1") (pinfunction "1_1") (pintype "passive"))
    )
    (net (code "51") (name "Net-(JACK-1)") (class "Default")
      (node (ref "F1") (pin "2") (pinfunction "2_2") (pintype "passive"))
      (node (ref "JACK") (pin "P1") (pinfunction "1_P1") (pintype "passive"))
    )
    (net (code "52") (name "Net-(R3-Pad1)") (class "Default")
      (node (ref "R3") (pin "1") (pinfunction "1_1") (pintype "passive"))
      (node (ref "TX1") (pin "A") (pinfunction "A_A") (pintype "bidirectional"))
    )
    (net (code "53") (name "Net-(R4-Pad1)") (class "Default")
      (node (ref "R4") (pin "1") (pinfunction "1_1") (pintype "passive"))
      (node (ref "RX1") (pin "A") (pinfunction "A_A") (pintype "bidirectional"))
    )
    (net (code "54") (name "Net-(R15-Pad1)") (class "Default")
      (node (ref "R15") (pin "1") (pinfunction "1_1") (pintype "passive"))
      (node (ref "STATE") (pin "A") (pinfunction "A_A") (pintype "bidirectional"))
    )
    (net (code "55") (name "Net-(USB-2)") (class "Default")
      (node (ref "IC1") (pin "P$1") (pinfunction "IO1_P$1") (pintype "bidirectional"))
      (node (ref "USB") (pin "P$2") (pinfunction "2_P$2") (pintype "bidirectional"))
    )
    (net (code "56") (name "Net-(USB-3)") (class "Default")
      (node (ref "IC1") (pin "P$3") (pinfunction "IO2_P$3") (pintype "bidirectional"))
      (node (ref "USB") (pin "P$3") (pinfunction "3_P$3") (pintype "bidirectional"))
    )
    (net (code "57") (name "Net-(USB-P$1)") (class "Default")
      (node (ref "RUSB") (pin "1") (pinfunction "1_1") (pintype "passive"))
      (node (ref "USB") (pin "SHIELD_1") (pinfunction "P$1_SHIELD_1") (pintype "bidirectional"))
    )
    (net (code "58") (name "Net-(USB-P$4)") (class "Default")
      (node (ref "CUSB") (pin "1") (pinfunction "1_1") (pintype "passive"))
      (node (ref "USB") (pin "SHIELD_4") (pinfunction "P$4_SHIELD_4") (pintype "bidirectional"))
    )
    (net (code "59") (name "OUT00") (class "Default")
      (node (ref "IC6") (pin "5") (pinfunction "PB1/ADC9_5") (pintype "bidirectional"))
      (node (ref "IC8") (pin "2") (pinfunction "P$2_2") (pintype "bidirectional"))
    )
    (net (code "60") (name "OUT01") (class "Default")
      (node (ref "IC6") (pin "40") (pinfunction "PA0/ADC0/AREF_40") (pintype "bidirectional"))
      (node (ref "IC9") (pin "2") (pinfunction "P$2_2") (pintype "bidirectional"))
    )
    (net (code "61") (name "OUT02") (class "Default")
      (node (ref "IC10") (pin "2") (pinfunction "P$2_2") (pintype "bidirectional"))
      (node (ref "IC6") (pin "41") (pinfunction "PA1/ADC1_41") (pintype "bidirectional"))
    )
    (net (code "62") (name "OUT03") (class "Default")
      (node (ref "IC11") (pin "2") (pinfunction "P$2_2") (pintype "bidirectional"))
      (node (ref "IC6") (pin "42") (pinfunction "PA2/ADC2_42") (pintype "bidirectional"))
    )
    (net (code "63") (name "OUT04") (class "Default")
      (node (ref "IC12") (pin "2") (pinfunction "P$2_2") (pintype "bidirectional"))
      (node (ref "IC6") (pin "43") (pinfunction "PA3/ADC3_43") (pintype "bidirectional"))
    )
    (net (code "64") (name "OUT05") (class "Default")
      (node (ref "IC13") (pin "2") (pinfunction "P$2_2") (pintype "bidirectional"))
      (node (ref "IC6") (pin "44") (pinfunction "PA4/ADC4_44") (pintype "bidirectional"))
    )
    (net (code "65") (name "OUT06") (class "Default")
      (node (ref "IC15") (pin "2") (pinfunction "P$2_2") (pintype "bidirectional"))
      (node (ref "IC6") (pin "1") (pinfunction "PA5/ADC5_1") (pintype "bidirectional"))
    )
    (net (code "66") (name "OUT07") (class "Default")
      (node (ref "IC16") (pin "2") (pinfunction "P$2_2") (pintype "bidirectional"))
      (node (ref "IC6") (pin "2") (pinfunction "PA6/ADC6_2") (pintype "bidirectional"))
    )
    (net (code "67") (name "OUT08") (class "Default")
      (node (ref "IC17") (pin "2") (pinfunction "P$2_2") (pintype "bidirectional"))
      (node (ref "IC6") (pin "3") (pinfunction "PA7/ADC7/AC0-OUT_3") (pintype "bidirectional"))
    )
    (net (code "68") (name "P5.45V") (class "Default")
      (node (ref "C12") (pin "1") (pinfunction "1_1") (pintype "passive"))
      (node (ref "C13") (pin "1") (pinfunction "1_1") (pintype "passive"))
      (node (ref "C14") (pin "1") (pinfunction "1_1") (pintype "passive"))
      (node (ref "IC2") (pin "P4") (pinfunction "VOUT_P4") (pintype "passive"))
      (node (ref "IC4") (pin "P$1") (pinfunction "EN_P$1") (pintype "bidirectional"))
      (node (ref "IC4") (pin "P$2") (pinfunction "IN_P$2") (pintype "bidirectional"))
      (node (ref "RTUNE") (pin "2") (pinfunction "2_2") (pintype "passive"))
    )
    (net (code "69") (name "PDI-CLK") (class "Default")
      (node (ref "IC6") (pin "35") (pinfunction "RESET/PDI-CLK_35") (pintype "input"))
      (node (ref "PDI") (pin "5") (pinfunction "5_5") (pintype "passive"))
    )
    (net (code "70") (name "PDI-DATA") (class "Default")
      (node (ref "IC6") (pin "34") (pinfunction "PDI-DATA_34") (pintype "bidirectional"))
      (node (ref "PDI") (pin "1") (pinfunction "1_1") (pintype "passive"))
    )
    (net (code "71") (name "RTS") (class "Default")
      (node (ref "IC5") (pin "13") (pinfunction "B2_13") (pintype "bidirectional"))
      (node (ref "IC6") (pin "28") (pinfunction "~{OC0ASDAPE0}_28") (pintype "bidirectional"))
    )
    (net (code "72") (name "RXD") (class "Default")
      (node (ref "IC5") (pin "12") (pinfunction "B3_12") (pintype "bidirectional"))
      (node (ref "IC6") (pin "33") (pinfunction "~TXD0OC0DPE3_33") (pintype "bidirectional"))
    )
    (net (code "73") (name "SCK0") (class "Default")
      (node (ref "IC6") (pin "17") (pinfunction "PC7/SCK/TXD1/CLKO/EVO_17") (pintype "bidirectional"))
      (node (ref "R28") (pin "1") (pinfunction "1_1") (pintype "passive"))
    )
    (net (code "74") (name "SCK0_T") (class "Default")
      (node (ref "J1") (pin "4") (pinfunction "4_4") (pintype "passive"))
      (node (ref "R28") (pin "2") (pinfunction "2_2") (pintype "passive"))
    )
    (net (code "75") (name "SCK1") (class "Default")
      (node (ref "IC6") (pin "27") (pinfunction "~~{TXD1SCKCLKOPD7}_27") (pintype "bidirectional"))
      (node (ref "R30") (pin "2") (pinfunction "2_2") (pintype "passive"))
    )
    (net (code "76") (name "SCK1_T") (class "Default")
      (node (ref "J2") (pin "4") (pinfunction "4_4") (pintype "passive"))
      (node (ref "R30") (pin "1") (pinfunction "1_1") (pintype "passive"))
    )
    (net (code "77") (name "STATE") (class "Default")
      (node (ref "IC6") (pin "36") (pinfunction "PR0/XTAL2_36") (pintype "bidirectional"))
      (node (ref "R15") (pin "2") (pinfunction "2_2") (pintype "passive"))
    )
    (net (code "78") (name "TXD") (class "Default")
      (node (ref "IC5") (pin "14") (pinfunction "B1_14") (pintype "bidirectional"))
      (node (ref "IC6") (pin "32") (pinfunction "~RXD0OC0CPE2_32") (pintype "bidirectional"))
    )
    (net (code "79") (name "USB5V") (class "Default")
      (node (ref "C11") (pin "1") (pinfunction "1_1") (pintype "passive"))
      (node (ref "C15") (pin "1") (pinfunction "1_1") (pintype "passive"))
      (node (ref "C8") (pin "1") (pinfunction "1_1") (pintype "passive"))
      (node (ref "C9") (pin "+") (pinfunction "+_+") (pintype "passive"))
      (node (ref "IC3") (pin "20") (pinfunction "VCC_20") (pintype "power_in"))
      (node (ref "IC3") (pin "4") (pinfunction "VCCIO_4") (pintype "power_in"))
      (node (ref "IC5") (pin "1") (pinfunction "VDD1_1") (pintype "bidirectional"))
      (node (ref "IC5") (pin "7") (pinfunction "NC/EN_7") (pintype "bidirectional"))
      (node (ref "L1") (pin "1") (pinfunction "1_1") (pintype "passive"))
      (node (ref "R3") (pin "2") (pinfunction "2_2") (pintype "passive"))
      (node (ref "R4") (pin "2") (pinfunction "2_2") (pintype "passive"))
    )
    (net (code "80") (name "USBDM") (class "Default")
      (node (ref "C5") (pin "1") (pinfunction "1_1") (pintype "passive"))
      (node (ref "IC1") (pin "P$6") (pinfunction "IO1_P$6") (pintype "bidirectional"))
      (node (ref "IC3") (pin "16") (pinfunction "USBDM_16") (pintype "bidirectional"))
    )
    (net (code "81") (name "USBDP") (class "Default")
      (node (ref "C4") (pin "1") (pinfunction "1_1") (pintype "passive"))
      (node (ref "IC1") (pin "P$4") (pinfunction "IO2_P$4") (pintype "bidirectional"))
      (node (ref "IC3") (pin "15") (pinfunction "USBDP_15") (pintype "bidirectional"))
    )
    (net (code "82") (name "VCCIO") (class "Default")
      (node (ref "C17") (pin "1") (pinfunction "1_1") (pintype "passive"))
      (node (ref "C19") (pin "1") (pinfunction "1_1") (pintype "passive"))
      (node (ref "C21") (pin "1") (pinfunction "1_1") (pintype "passive"))
      (node (ref "C22") (pin "1") (pinfunction "1_1") (pintype "passive"))
      (node (ref "C23") (pin "1") (pinfunction "1_1") (pintype "passive"))
      (node (ref "C24") (pin "1") (pinfunction "1_1") (pintype "passive"))
      (node (ref "C25") (pin "1") (pinfunction "1_1") (pintype "passive"))
      (node (ref "C26") (pin "1") (pinfunction "1_1") (pintype "passive"))
      (node (ref "C27") (pin "1") (pinfunction "1_1") (pintype "passive"))
      (node (ref "C34") (pin "1") (pinfunction "1_1") (pintype "passive"))
      (node (ref "CLKIN") (pin "1") (pinfunction "1_1") (pintype "passive"))
      (node (ref "IC14") (pin "5") (pinfunction "P$5_5") (pintype "bidirectional"))
      (node (ref "IC5") (pin "10") (pinfunction "NC/EN_10") (pintype "bidirectional"))
      (node (ref "IC5") (pin "16") (pinfunction "VDD2_16") (pintype "bidirectional"))
      (node (ref "IC6") (pin "19") (pinfunction "VCC_19") (pintype "power_in"))
      (node (ref "IC6") (pin "31") (pinfunction "VCC_31") (pintype "power_in"))
      (node (ref "IC6") (pin "39") (pinfunction "AVCC_39") (pintype "power_in"))
      (node (ref "IC6") (pin "9") (pinfunction "VCC_9") (pintype "power_in"))
      (node (ref "IC7") (pin "5") (pinfunction "OUT_5") (pintype "bidirectional"))
      (node (ref "J3") (pin "3") (pinfunction "3_3") (pintype "passive"))
      (node (ref "OSC1") (pin "P$4") (pinfunction "VDD_P$4") (pintype "passive"))
      (node (ref "PDI") (pin "2") (pinfunction "2_2") (pintype "passive"))
      (node (ref "R11") (pin "2") (pinfunction "2_2") (pintype "passive"))
      (node (ref "R13") (pin "2") (pinfunction "2_2") (pintype "passive"))
      (node (ref "R7") (pin "2") (pinfunction "2_2") (pintype "passive"))
      (node (ref "R9") (pin "2") (pinfunction "2_2") (pintype "passive"))
    )
    (net (code "83") (name "unconnected-(IC3-CBUS2-Pad13)") (class "Default")
      (node (ref "IC3") (pin "13") (pinfunction "CBUS2_13") (pintype "bidirectional"))
    )
    (net (code "84") (name "unconnected-(IC3-CBUS3-Pad14)") (class "Default")
      (node (ref "IC3") (pin "14") (pinfunction "CBUS3_14") (pintype "bidirectional"))
    )
    (net (code "85") (name "unconnected-(IC3-CBUS4-Pad12)") (class "Default")
      (node (ref "IC3") (pin "12") (pinfunction "CBUS4_12") (pintype "bidirectional"))
    )
    (net (code "86") (name "unconnected-(IC3-OSCI-Pad27)") (class "Default")
      (node (ref "IC3") (pin "27") (pinfunction "OSCI_27") (pintype "input"))
    )
    (net (code "87") (name "unconnected-(IC3-OSCO-Pad28)") (class "Default")
      (node (ref "IC3") (pin "28") (pinfunction "OSCO_28") (pintype "output"))
    )
    (net (code "88") (name "unconnected-(IC3-~{DCD}-Pad10)") (class "Default")
      (node (ref "IC3") (pin "10") (pinfunction "~{DCD}_10") (pintype "input"))
    )
    (net (code "89") (name "unconnected-(IC3-~{DSR}-Pad9)") (class "Default")
      (node (ref "IC3") (pin "9") (pinfunction "~{DSR}_9") (pintype "input"))
    )
    (net (code "90") (name "unconnected-(IC3-~{DTR}-Pad2)") (class "Default")
      (node (ref "IC3") (pin "2") (pinfunction "~{DTR}_2") (pintype "output"))
    )
    (net (code "91") (name "unconnected-(IC3-~{RESET}-Pad19)") (class "Default")
      (node (ref "IC3") (pin "19") (pinfunction "~{RESET}_19") (pintype "input"))
    )
    (net (code "92") (name "unconnected-(IC3-~{RI}-Pad6)") (class "Default")
      (node (ref "IC3") (pin "6") (pinfunction "~{RI}_6") (pintype "input"))
    )
    (net (code "93") (name "unconnected-(IC6-PB2{slash}ADC10{slash}DAC0-Pad6)") (class "Default")
      (node (ref "IC6") (pin "6") (pinfunction "PB2/ADC10/DAC0_6") (pintype "bidirectional"))
    )
    (net (code "94") (name "unconnected-(IC6-PB3{slash}ADC11{slash}DAC1-Pad7)") (class "Default")
      (node (ref "IC6") (pin "7") (pinfunction "PB3/ADC11/DAC1_7") (pintype "bidirectional"))
    )
    (net (code "95") (name "unconnected-(IC6-PC3{slash}OC0D{slash}TXD0-Pad13)") (class "Default")
      (node (ref "IC6") (pin "13") (pinfunction "PC3/OC0D/TXD0_13") (pintype "bidirectional"))
    )
    (net (code "96") (name "unconnected-(IC6-~OC0CRXD0PD2-Pad22)") (class "Default")
      (node (ref "IC6") (pin "22") (pinfunction "~OC0CRXD0PD2_22") (pintype "bidirectional"))
    )
    (net (code "97") (name "unconnected-(IC6-~OC0DTXD0PD3-Pad23)") (class "Default")
      (node (ref "IC6") (pin "23") (pinfunction "~OC0DTXD0PD3_23") (pintype "bidirectional"))
    )
    (net (code "98") (name "unconnected-(IC7-N{slash}C-Pad4)") (class "Default")
      (node (ref "IC7") (pin "4") (pinfunction "N/C_4") (pintype "bidirectional"))
    )
    (net (code "99") (name "unconnected-(OSC1-STANDBY#-PadP$1)") (class "Default")
      (node (ref "OSC1") (pin "P$1") (pinfunction "STANDBY#_P$1") (pintype "passive"))
    )
    (net (code "100") (name "unconnected-(PDI-Pad3)") (class "Default")
      (node (ref "PDI") (pin "3") (pinfunction "3_3") (pintype "passive"))
    )
    (net (code "101") (name "unconnected-(PDI-Pad4)") (class "Default")
      (node (ref "PDI") (pin "4") (pinfunction "4_4") (pintype "passive"))
    )
    (net (code "102") (name "unconnected-(USB-4-PadP$4)") (class "Default")
      (node (ref "USB") (pin "P$4") (pinfunction "4_P$4") (pintype "bidirectional"))
    )
    (net (code "103") (name "unconnected-(USB-P$2-PadSHIELD_2)") (class "Default")
      (node (ref "USB") (pin "SHIELD_2") (pinfunction "P$2_SHIELD_2") (pintype "bidirectional"))
    )
    (net (code "104") (name "unconnected-(USB-P$3-PadSHIELD_3)") (class "Default")
      (node (ref "USB") (pin "SHIELD_3") (pinfunction "P$3_SHIELD_3") (pintype "bidirectional"))
    )
    (net (code "105") (name "~{CS0_0}") (class "Default")
      (node (ref "IC6") (pin "14") (pinfunction "PC4/OC1A/#SS_14") (pintype "bidirectional"))
      (node (ref "J1") (pin "3") (pinfunction "3_3") (pintype "passive"))
    )
    (net (code "106") (name "~{CS0_1}") (class "Default")
      (node (ref "IC6") (pin "10") (pinfunction "PC0/OC0A/SDA_10") (pintype "bidirectional"))
      (node (ref "J1") (pin "2") (pinfunction "2_2") (pintype "passive"))
      (node (ref "R7") (pin "1") (pinfunction "1_1") (pintype "passive"))
      (node (ref "R8") (pin "2") (pinfunction "2_2") (pintype "passive"))
    )
    (net (code "107") (name "~{CS0_2}") (class "Default")
      (node (ref "IC6") (pin "11") (pinfunction "PC1/OC0B/XCK0/SCL_11") (pintype "bidirectional"))
      (node (ref "J1") (pin "1") (pinfunction "1_1") (pintype "passive"))
      (node (ref "R11") (pin "1") (pinfunction "1_1") (pintype "passive"))
      (node (ref "R12") (pin "2") (pinfunction "2_2") (pintype "passive"))
    )
    (net (code "108") (name "~{CS1_0}") (class "Default")
      (node (ref "IC6") (pin "24") (pinfunction "~{#SSPD4}_24") (pintype "bidirectional"))
      (node (ref "J2") (pin "3") (pinfunction "3_3") (pintype "passive"))
    )
    (net (code "109") (name "~{CS1_1}") (class "Default")
      (node (ref "IC6") (pin "20") (pinfunction "~{OC0APD0}_20") (pintype "bidirectional"))
      (node (ref "J2") (pin "2") (pinfunction "2_2") (pintype "passive"))
      (node (ref "R10") (pin "2") (pinfunction "2_2") (pintype "passive"))
      (node (ref "R9") (pin "1") (pinfunction "1_1") (pintype "passive"))
    )
    (net (code "110") (name "~{CS1_2}") (class "Default")
      (node (ref "IC6") (pin "21") (pinfunction "~OC0BXCK0PD1_21") (pintype "bidirectional"))
      (node (ref "J2") (pin "1") (pinfunction "1_1") (pintype "passive"))
      (node (ref "R13") (pin "1") (pinfunction "1_1") (pintype "passive"))
      (node (ref "R14") (pin "2") (pinfunction "2_2") (pintype "passive"))
    )
  )
)
